# glowbs_4.net
KiCad netlist of a schematic drawn in EAGLE
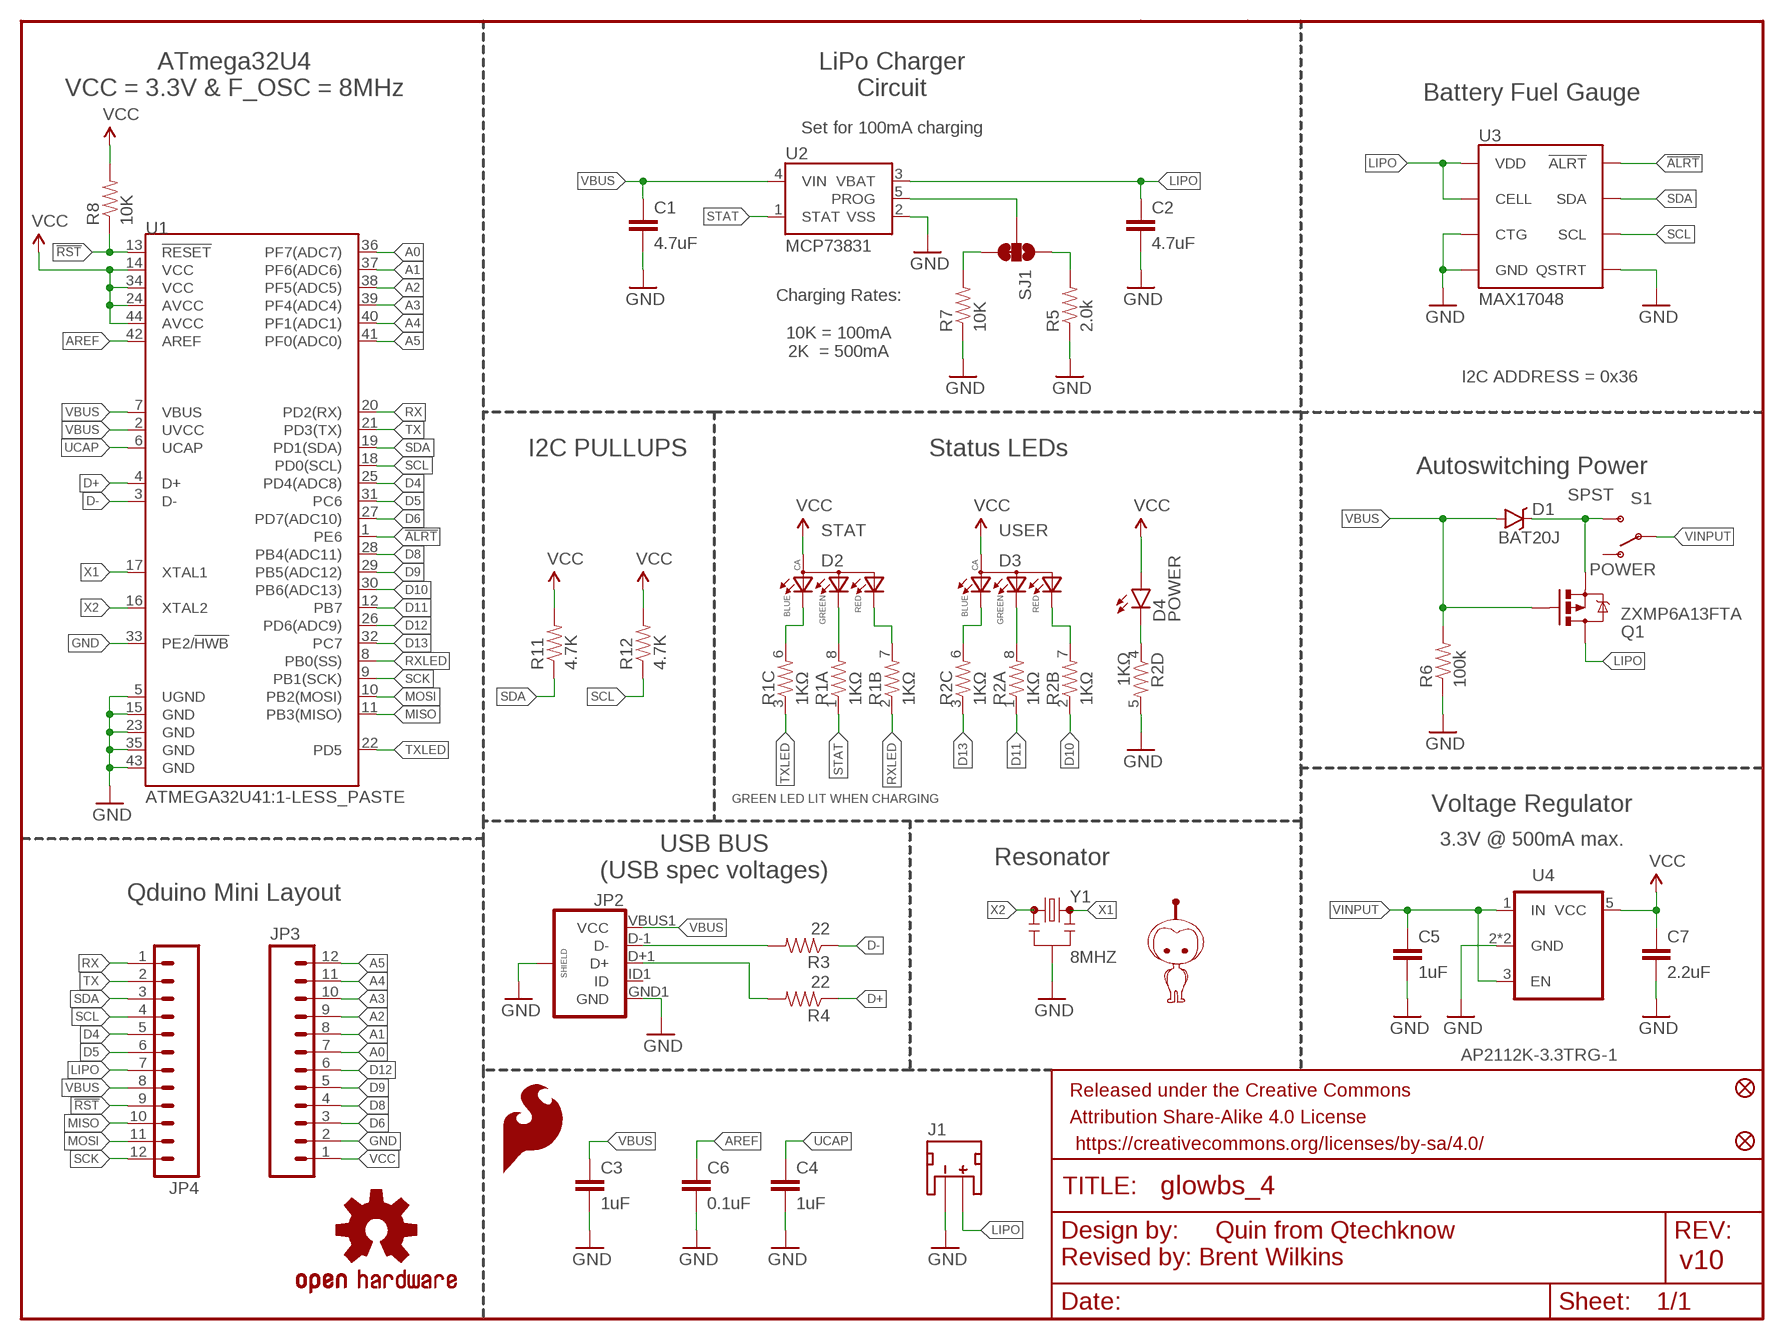
[diagram p0: schematic, sheet 1]

(export (version "E")
  (design (tool "Eeschema 10.0.6"))
  (components
    (comp (ref "C1")
      (value "4.7uF")
      (footprint "eagle-import:0603-CAP")
      (libsource (lib "eagle-import") (part "CAP0603-CAP"))
    )
    (comp (ref "C2")
      (value "4.7uF")
      (footprint "eagle-import:0603-CAP")
      (libsource (lib "eagle-import") (part "CAP0603-CAP"))
    )
    (comp (ref "C3")
      (value "1uF")
      (footprint "eagle-import:0603-CAP")
      (libsource (lib "eagle-import") (part "CAP0603-CAP"))
    )
    (comp (ref "C4")
      (value "1uF")
      (footprint "eagle-import:0603-CAP")
      (libsource (lib "eagle-import") (part "CAP0603-CAP"))
    )
    (comp (ref "C5")
      (value "1uF")
      (footprint "eagle-import:0603-CAP")
      (libsource (lib "eagle-import") (part "CAP0603-CAP"))
    )
    (comp (ref "C6")
      (value "0.1uF")
      (footprint "eagle-import:0603-CAP")
      (libsource (lib "eagle-import") (part "0.1UF-25V(+80/-20%)(0603)"))
    )
    (comp (ref "C7")
      (value "2.2uF")
      (footprint "eagle-import:0603-CAP")
      (libsource (lib "eagle-import") (part "2.2UF-10V-20%(0603)"))
    )
    (comp (ref "D1")
      (value "BAT20J")
      (footprint "eagle-import:SOD-323")
      (libsource (lib "eagle-import") (part "DIODE-SCHOTTKY-BAT20J"))
    )
    (comp (ref "D2")
      (value "0.13_RGB_LEDPLCC")
      (footprint "eagle-import:P-LCC-4-3")
      (fields (field (name "PROD_ID") "DIO-12986"))
      (libsource (lib "eagle-import") (part "0.13_RGB_LEDPLCC"))
    )
    (comp (ref "D3")
      (value "0.13_RGB_LEDPLCC")
      (footprint "eagle-import:P-LCC-4-3")
      (libsource (lib "eagle-import") (part "0.13_RGB_LEDPLCC"))
    )
    (comp (ref "D4")
      (value "POWER")
      (footprint "eagle-import:LED-0603")
      (fields (field (name "PROD_ID") "DIO-00821"))
      (libsource (lib "eagle-import") (part "LED-GREEN0603"))
    )
    (comp (ref "FID1")
      (value "FIDUCIALUFIDUCIAL")
      (footprint "eagle-import:MICRO-FIDUCIAL")
      (libsource (lib "eagle-import") (part "FIDUCIALUFIDUCIAL"))
    )
    (comp (ref "FID2")
      (value "FIDUCIALUFIDUCIAL")
      (footprint "eagle-import:MICRO-FIDUCIAL")
      (libsource (lib "eagle-import") (part "FIDUCIALUFIDUCIAL"))
    )
    (comp (ref "FRAME2")
      (value "FRAME-LETTER")
      (footprint "eagle-import:CREATIVE_COMMONS")
      (fields (field (name "DESIGNER") "NAME"))
      (libsource (lib "eagle-import") (part "FRAME-LETTER"))
    )
    (comp (ref "J1")
      (value "LiPo")
      (footprint "eagle-import:JST-2-SMD")
      (libsource (lib "eagle-import") (part "JST_2MM_MALE"))
    )
    (comp (ref "JP2")
      (value "USB_MICROB_PLUGCONN-11752")
      (footprint "eagle-import:USB-B-MICRO-SMD_V03")
      (libsource (lib "eagle-import") (part "USB_MICROB_PLUGCONN-11752"))
    )
    (comp (ref "JP3")
      (value "M12PTH")
      (footprint "eagle-import:1X12")
      (libsource (lib "eagle-import") (part "M12PTH"))
    )
    (comp (ref "JP4")
      (value "M12PTH")
      (footprint "eagle-import:1X12")
      (libsource (lib "eagle-import") (part "M12PTH"))
    )
    (comp (ref "LOGO1")
      (value "OSHW-LOGOS")
      (footprint "eagle-import:OSHW-LOGO-S")
      (libsource (lib "eagle-import") (part "OSHW-LOGOS"))
    )
    (comp (ref "LOGO2")
      (value "SFE_LOGO_FLAME.1_INCH")
      (footprint "eagle-import:SFE_LOGO_FLAME_.1")
      (libsource (lib "eagle-import") (part "SFE_LOGO_FLAME.1_INCH"))
    )
    (comp (ref "Q1")
      (value "ZXMP6A13FTA")
      (footprint "eagle-import:SOT23-3")
      (libsource (lib "eagle-import") (part "MOSFET-PCHANNEL"))
    )
    (comp (ref "R1")
      (value "1KΩ")
      (footprint "eagle-import:0603-ARV")
      (fields (field (name "PROD_ID") "RES-12985"))
      (libsource (lib "eagle-import") (part "RESISTOR-ARRAY0603-ARV"))
    )
    (comp (ref "R2")
      (value "1KΩ")
      (footprint "eagle-import:0603-ARV")
      (fields (field (name "PROD_ID") "RES-12985"))
      (libsource (lib "eagle-import") (part "RESISTOR-ARRAY0603-ARV"))
    )
    (comp (ref "R3")
      (value "22")
      (footprint "eagle-import:0603-RES")
      (libsource (lib "eagle-import") (part "RESISTOR0603"))
    )
    (comp (ref "R4")
      (value "22")
      (footprint "eagle-import:0603-RES")
      (libsource (lib "eagle-import") (part "RESISTOR0603"))
    )
    (comp (ref "R5")
      (value "2.0k")
      (footprint "eagle-import:0603-RES")
      (libsource (lib "eagle-import") (part "2.0KOHM1/10W5%(0603)"))
    )
    (comp (ref "R6")
      (value "100k")
      (footprint "eagle-import:0603-RES")
      (libsource (lib "eagle-import") (part "100KOHM-1/10W-1%(0603)"))
    )
    (comp (ref "R7")
      (value "10K")
      (footprint "eagle-import:0603-RES")
      (libsource (lib "eagle-import") (part "10KOHM-1/10W-1%(0603)0603"))
    )
    (comp (ref "R8")
      (value "10K")
      (footprint "eagle-import:0603-RES")
      (libsource (lib "eagle-import") (part "10KOHM-1/10W-1%(0603)0603"))
    )
    (comp (ref "R11")
      (value "4.7K")
      (footprint "eagle-import:0603-RES")
      (libsource (lib "eagle-import") (part "RESISTOR0603-RES"))
    )
    (comp (ref "R12")
      (value "4.7K")
      (footprint "eagle-import:0603-RES")
      (libsource (lib "eagle-import") (part "RESISTOR0603-RES"))
    )
    (comp (ref "S1")
      (value "POWER")
      (footprint "eagle-import:SWITCH-SPST-SMD-A")
      (libsource (lib "eagle-import") (part "SWITCH-SPDT-SMD-A"))
    )
    (comp (ref "SJ1")
      (value "JUMPER-PAD-3-2OF3_NC_BY_TRACE_SMALL")
      (footprint "eagle-import:PAD-JUMPER-3-2OF3_NC_BY_TRACE_YES_SILK_FULL_BOX")
      (libsource (lib "eagle-import") (part "JUMPER-PAD-3-2OF3_NC_BY_TRACE_SMALL"))
    )
    (comp (ref "U1")
      (value "ATMEGA32U41:1-LESS_PASTE")
      (footprint "eagle-import:QFN-44-NOPAD_1_1-LESS_PASTE")
      (libsource (lib "eagle-import") (part "ATMEGA32U41{colon}1-LESS_PASTE"))
    )
    (comp (ref "U2")
      (value "MCP73831")
      (footprint "eagle-import:SOT23-5")
      (libsource (lib "eagle-import") (part "MCP73831"))
    )
    (comp (ref "U3")
      (value "MAX17048")
      (footprint "eagle-import:DFN-8")
      (libsource (lib "eagle-import") (part "MAX17048DFN8"))
    )
    (comp (ref "U4")
      (value "AP2112K-3.3TRG-1")
      (footprint "eagle-import:SOT23-5")
      (libsource (lib "eagle-import") (part "LDO-TPS78233"))
    )
    (comp (ref "U5")
      (value "MIGHTYQ-L-SILK")
      (footprint "eagle-import:LOGO-LARGE-SILK")
      (libsource (lib "eagle-import") (part "MIGHTYQ-L-SILK"))
    )
    (comp (ref "Y1")
      (value "8MHZ")
      (footprint "eagle-import:RESONATOR-SMD")
      (libsource (lib "eagle-import") (part "RESONATOR8MHZ"))
    )
  )
  (nets
    (net (code "1") (name "/~{ALRT}") (class "Default")
      (node (ref "U1") (pin "1") (pinfunction "PE6_1") (pintype "bidirectional"))
      (node (ref "U3") (pin "P$5") (pinfunction "~{ALRT}_P$5") (pintype "bidirectional"))
    )
    (net (code "2") (name "/~{RST}") (class "Default")
      (node (ref "JP4") (pin "9") (pinfunction "9_9") (pintype "passive"))
      (node (ref "R8") (pin "1") (pinfunction "1_1") (pintype "passive"))
      (node (ref "U1") (pin "13") (pinfunction "~{RESET}_13") (pintype "bidirectional"))
    )
    (net (code "3") (name "A0") (class "Default")
      (node (ref "JP3") (pin "7") (pinfunction "7_7") (pintype "passive"))
      (node (ref "U1") (pin "36") (pinfunction "PF7(ADC7)_36") (pintype "bidirectional"))
    )
    (net (code "4") (name "A1") (class "Default")
      (node (ref "JP3") (pin "8") (pinfunction "8_8") (pintype "passive"))
      (node (ref "U1") (pin "37") (pinfunction "PF6(ADC6)_37") (pintype "bidirectional"))
    )
    (net (code "5") (name "A2") (class "Default")
      (node (ref "JP3") (pin "9") (pinfunction "9_9") (pintype "passive"))
      (node (ref "U1") (pin "38") (pinfunction "PF5(ADC5)_38") (pintype "bidirectional"))
    )
    (net (code "6") (name "A3") (class "Default")
      (node (ref "JP3") (pin "10") (pinfunction "10_10") (pintype "passive"))
      (node (ref "U1") (pin "39") (pinfunction "PF4(ADC4)_39") (pintype "bidirectional"))
    )
    (net (code "7") (name "A4") (class "Default")
      (node (ref "JP3") (pin "11") (pinfunction "11_11") (pintype "passive"))
      (node (ref "U1") (pin "40") (pinfunction "PF1(ADC1)_40") (pintype "bidirectional"))
    )
    (net (code "8") (name "A5") (class "Default")
      (node (ref "JP3") (pin "12") (pinfunction "12_12") (pintype "passive"))
      (node (ref "U1") (pin "41") (pinfunction "PF0(ADC0)_41") (pintype "bidirectional"))
    )
    (net (code "9") (name "AREF") (class "Default")
      (node (ref "C6") (pin "1") (pinfunction "1_1") (pintype "passive"))
      (node (ref "U1") (pin "42") (pinfunction "AREF_42") (pintype "bidirectional"))
    )
    (net (code "10") (name "D+") (class "Default")
      (node (ref "R4") (pin "1") (pinfunction "1_1") (pintype "passive"))
      (node (ref "U1") (pin "4") (pinfunction "D+_4") (pintype "bidirectional"))
    )
    (net (code "11") (name "D-") (class "Default")
      (node (ref "R3") (pin "1") (pinfunction "1_1") (pintype "passive"))
      (node (ref "U1") (pin "3") (pinfunction "D-_3") (pintype "bidirectional"))
    )
    (net (code "12") (name "D4") (class "Default")
      (node (ref "JP4") (pin "5") (pinfunction "5_5") (pintype "passive"))
      (node (ref "U1") (pin "25") (pinfunction "PD4(ADC8)_25") (pintype "bidirectional"))
    )
    (net (code "13") (name "D5") (class "Default")
      (node (ref "JP4") (pin "6") (pinfunction "6_6") (pintype "passive"))
      (node (ref "U1") (pin "31") (pinfunction "PC6_31") (pintype "bidirectional"))
    )
    (net (code "14") (name "D6") (class "Default")
      (node (ref "JP3") (pin "3") (pinfunction "3_3") (pintype "passive"))
      (node (ref "U1") (pin "27") (pinfunction "PD7(ADC10)_27") (pintype "bidirectional"))
    )
    (net (code "15") (name "D8") (class "Default")
      (node (ref "JP3") (pin "4") (pinfunction "4_4") (pintype "passive"))
      (node (ref "U1") (pin "28") (pinfunction "PB4(ADC11)_28") (pintype "bidirectional"))
    )
    (net (code "16") (name "D9") (class "Default")
      (node (ref "JP3") (pin "5") (pinfunction "5_5") (pintype "passive"))
      (node (ref "U1") (pin "29") (pinfunction "PB5(ADC12)_29") (pintype "bidirectional"))
    )
    (net (code "17") (name "D10") (class "Default")
      (node (ref "R2") (pin "2") (pinfunction "1_2") (pintype "passive"))
      (node (ref "U1") (pin "30") (pinfunction "PB6(ADC13)_30") (pintype "bidirectional"))
    )
    (net (code "18") (name "D11") (class "Default")
      (node (ref "R2") (pin "1") (pinfunction "1_1") (pintype "passive"))
      (node (ref "U1") (pin "12") (pinfunction "PB7_12") (pintype "bidirectional"))
    )
    (net (code "19") (name "D12") (class "Default")
      (node (ref "JP3") (pin "6") (pinfunction "6_6") (pintype "passive"))
      (node (ref "U1") (pin "26") (pinfunction "PD6(ADC9)_26") (pintype "bidirectional"))
    )
    (net (code "20") (name "D13") (class "Default")
      (node (ref "R2") (pin "3") (pinfunction "1_3") (pintype "passive"))
      (node (ref "U1") (pin "32") (pinfunction "PC7_32") (pintype "bidirectional"))
    )
    (net (code "21") (name "GND") (class "Default")
      (node (ref "C1") (pin "2") (pinfunction "2_2") (pintype "passive"))
      (node (ref "C2") (pin "2") (pinfunction "2_2") (pintype "passive"))
      (node (ref "C3") (pin "2") (pinfunction "2_2") (pintype "passive"))
      (node (ref "C4") (pin "2") (pinfunction "2_2") (pintype "passive"))
      (node (ref "C5") (pin "2") (pinfunction "2_2") (pintype "passive"))
      (node (ref "C6") (pin "2") (pinfunction "2_2") (pintype "passive"))
      (node (ref "C7") (pin "2") (pinfunction "2_2") (pintype "passive"))
      (node (ref "J1") (pin "1") (pinfunction "-_1") (pintype "bidirectional"))
      (node (ref "JP2") (pin "GND1") (pinfunction "GND_GND1") (pintype "bidirectional"))
      (node (ref "JP2") (pin "SHIELD1") (pinfunction "SHIELD_SHIELD1") (pintype "bidirectional"))
      (node (ref "JP2") (pin "SHIELD2") (pinfunction "SHIELD_SHIELD2") (pintype "bidirectional"))
      (node (ref "JP2") (pin "SHIELD3") (pinfunction "SHIELD_SHIELD3") (pintype "bidirectional"))
      (node (ref "JP3") (pin "2") (pinfunction "2_2") (pintype "passive"))
      (node (ref "R2") (pin "5") (pinfunction "2_5") (pintype "passive"))
      (node (ref "R5") (pin "1") (pinfunction "1_1") (pintype "passive"))
      (node (ref "R6") (pin "1") (pinfunction "1_1") (pintype "passive"))
      (node (ref "R7") (pin "1") (pinfunction "1_1") (pintype "passive"))
      (node (ref "U1") (pin "15") (pinfunction "GND_15") (pintype "bidirectional"))
      (node (ref "U1") (pin "23") (pinfunction "GND_23") (pintype "bidirectional"))
      (node (ref "U1") (pin "33") (pinfunction "PE2/~{HWB}_33") (pintype "bidirectional"))
      (node (ref "U1") (pin "35") (pinfunction "GND_35") (pintype "bidirectional"))
      (node (ref "U1") (pin "43") (pinfunction "GND_43") (pintype "bidirectional"))
      (node (ref "U1") (pin "5") (pinfunction "UGND_5") (pintype "bidirectional"))
      (node (ref "U2") (pin "2") (pinfunction "VSS_2") (pintype "power_in"))
      (node (ref "U3") (pin "P$1") (pinfunction "CTG_P$1") (pintype "input"))
      (node (ref "U3") (pin "P$4") (pinfunction "GND_P$4") (pintype "bidirectional"))
      (node (ref "U3") (pin "P$6") (pinfunction "QSTRT_P$6") (pintype "bidirectional"))
      (node (ref "U3") (pin "P$9") (pinfunction "GND_P$9") (pintype "bidirectional"))
      (node (ref "U4") (pin "2") (pinfunction "GND_2") (pintype "input"))
      (node (ref "U4") (pin "4") (pinfunction "GND_4") (pintype "input"))
      (node (ref "Y1") (pin "2") (pinfunction "2_2") (pintype "passive"))
    )
    (net (code "22") (name "LIPO") (class "Default")
      (node (ref "C2") (pin "1") (pinfunction "1_1") (pintype "passive"))
      (node (ref "J1") (pin "2") (pinfunction "+_2") (pintype "bidirectional"))
      (node (ref "JP4") (pin "7") (pinfunction "7_7") (pintype "passive"))
      (node (ref "Q1") (pin "3") (pinfunction "D_3") (pintype "passive"))
      (node (ref "U2") (pin "3") (pinfunction "VBAT_3") (pintype "power_in"))
      (node (ref "U3") (pin "P$2") (pinfunction "CELL_P$2") (pintype "input"))
      (node (ref "U3") (pin "P$3") (pinfunction "VDD_P$3") (pintype "bidirectional"))
    )
    (net (code "23") (name "MISO") (class "Default")
      (node (ref "JP4") (pin "10") (pinfunction "10_10") (pintype "passive"))
      (node (ref "U1") (pin "11") (pinfunction "PB3(MISO)_11") (pintype "bidirectional"))
    )
    (net (code "24") (name "MOSI") (class "Default")
      (node (ref "JP4") (pin "11") (pinfunction "11_11") (pintype "passive"))
      (node (ref "U1") (pin "10") (pinfunction "PB2(MOSI)_10") (pintype "bidirectional"))
    )
    (net (code "25") (name "Net-(D2-BLUE)") (class "Default")
      (node (ref "D2") (pin "3") (pinfunction "BLUE_3") (pintype "passive"))
      (node (ref "R1") (pin "6") (pinfunction "2_6") (pintype "passive"))
    )
    (net (code "26") (name "Net-(D2-GREEN)") (class "Default")
      (node (ref "D2") (pin "2") (pinfunction "GREEN_2") (pintype "passive"))
      (node (ref "R1") (pin "8") (pinfunction "2_8") (pintype "passive"))
    )
    (net (code "27") (name "Net-(D2-RED)") (class "Default")
      (node (ref "D2") (pin "1") (pinfunction "RED_1") (pintype "passive"))
      (node (ref "R1") (pin "7") (pinfunction "2_7") (pintype "passive"))
    )
    (net (code "28") (name "Net-(D3-BLUE)") (class "Default")
      (node (ref "D3") (pin "3") (pinfunction "BLUE_3") (pintype "passive"))
      (node (ref "R2") (pin "6") (pinfunction "2_6") (pintype "passive"))
    )
    (net (code "29") (name "Net-(D3-GREEN)") (class "Default")
      (node (ref "D3") (pin "2") (pinfunction "GREEN_2") (pintype "passive"))
      (node (ref "R2") (pin "8") (pinfunction "2_8") (pintype "passive"))
    )
    (net (code "30") (name "Net-(D3-RED)") (class "Default")
      (node (ref "D3") (pin "1") (pinfunction "RED_1") (pintype "passive"))
      (node (ref "R2") (pin "7") (pinfunction "2_7") (pintype "passive"))
    )
    (net (code "31") (name "Net-(JP2-D+)") (class "Default")
      (node (ref "JP2") (pin "D+1") (pinfunction "D+_D+1") (pintype "bidirectional"))
      (node (ref "R4") (pin "2") (pinfunction "2_2") (pintype "passive"))
    )
    (net (code "32") (name "Net-(JP2-D-)") (class "Default")
      (node (ref "JP2") (pin "D-1") (pinfunction "D-_D-1") (pintype "bidirectional"))
      (node (ref "R3") (pin "2") (pinfunction "2_2") (pintype "passive"))
    )
    (net (code "33") (name "Net-(Q1-S)") (class "Default")
      (node (ref "D1") (pin "C") (pinfunction "C_C") (pintype "passive"))
      (node (ref "Q1") (pin "2") (pinfunction "S_2") (pintype "passive"))
      (node (ref "S1") (pin "3") (pinfunction "S_3") (pintype "passive"))
    )
    (net (code "34") (name "Net-(R2D-1)") (class "Default")
      (node (ref "D4") (pin "C") (pinfunction "C_C") (pintype "passive"))
      (node (ref "R2") (pin "4") (pinfunction "1_4") (pintype "passive"))
    )
    (net (code "35") (name "Net-(R5-Pad2)") (class "Default")
      (node (ref "R5") (pin "2") (pinfunction "2_2") (pintype "passive"))
      (node (ref "SJ1") (pin "1") (pinfunction "1_1") (pintype "passive"))
    )
    (net (code "36") (name "Net-(R7-Pad2)") (class "Default")
      (node (ref "R7") (pin "2") (pinfunction "2_2") (pintype "passive"))
      (node (ref "SJ1") (pin "3") (pinfunction "3_3") (pintype "passive"))
    )
    (net (code "37") (name "Net-(U2-PROG)") (class "Default")
      (node (ref "SJ1") (pin "2") (pinfunction "2_2") (pintype "passive"))
      (node (ref "U2") (pin "5") (pinfunction "PROG_5") (pintype "input"))
    )
    (net (code "38") (name "RX") (class "Default")
      (node (ref "JP4") (pin "1") (pinfunction "1_1") (pintype "passive"))
      (node (ref "U1") (pin "20") (pinfunction "PD2(RX)_20") (pintype "bidirectional"))
    )
    (net (code "39") (name "RXLED") (class "Default")
      (node (ref "R1") (pin "2") (pinfunction "1_2") (pintype "passive"))
      (node (ref "U1") (pin "8") (pinfunction "PB0(SS)_8") (pintype "bidirectional"))
    )
    (net (code "40") (name "SCK") (class "Default")
      (node (ref "JP4") (pin "12") (pinfunction "12_12") (pintype "passive"))
      (node (ref "U1") (pin "9") (pinfunction "PB1(SCK)_9") (pintype "bidirectional"))
    )
    (net (code "41") (name "SCL") (class "Default")
      (node (ref "JP4") (pin "4") (pinfunction "4_4") (pintype "passive"))
      (node (ref "R12") (pin "1") (pinfunction "1_1") (pintype "passive"))
      (node (ref "U1") (pin "18") (pinfunction "PD0(SCL)_18") (pintype "bidirectional"))
      (node (ref "U3") (pin "P$7") (pinfunction "SCL_P$7") (pintype "output"))
    )
    (net (code "42") (name "SDA") (class "Default")
      (node (ref "JP4") (pin "3") (pinfunction "3_3") (pintype "passive"))
      (node (ref "R11") (pin "1") (pinfunction "1_1") (pintype "passive"))
      (node (ref "U1") (pin "19") (pinfunction "PD1(SDA)_19") (pintype "bidirectional"))
      (node (ref "U3") (pin "P$8") (pinfunction "SDA_P$8") (pintype "input"))
    )
    (net (code "43") (name "STAT") (class "Default")
      (node (ref "R1") (pin "1") (pinfunction "1_1") (pintype "passive"))
      (node (ref "U2") (pin "1") (pinfunction "STAT_1") (pintype "output"))
    )
    (net (code "44") (name "TX") (class "Default")
      (node (ref "JP4") (pin "2") (pinfunction "2_2") (pintype "passive"))
      (node (ref "U1") (pin "21") (pinfunction "PD3(TX)_21") (pintype "bidirectional"))
    )
    (net (code "45") (name "TXLED") (class "Default")
      (node (ref "R1") (pin "3") (pinfunction "1_3") (pintype "passive"))
      (node (ref "U1") (pin "22") (pinfunction "PD5_22") (pintype "bidirectional"))
    )
    (net (code "46") (name "UCAP") (class "Default")
      (node (ref "C4") (pin "1") (pinfunction "1_1") (pintype "passive"))
      (node (ref "U1") (pin "6") (pinfunction "UCAP_6") (pintype "bidirectional"))
    )
    (net (code "47") (name "VBUS") (class "Default")
      (node (ref "C1") (pin "1") (pinfunction "1_1") (pintype "passive"))
      (node (ref "C3") (pin "1") (pinfunction "1_1") (pintype "passive"))
      (node (ref "D1") (pin "A") (pinfunction "A_A") (pintype "passive"))
      (node (ref "JP2") (pin "VBUS1") (pinfunction "VCC_VBUS1") (pintype "bidirectional"))
      (node (ref "JP4") (pin "8") (pinfunction "8_8") (pintype "passive"))
      (node (ref "Q1") (pin "1") (pinfunction "G_1") (pintype "passive"))
      (node (ref "R6") (pin "2") (pinfunction "2_2") (pintype "passive"))
      (node (ref "U1") (pin "2") (pinfunction "UVCC_2") (pintype "bidirectional"))
      (node (ref "U1") (pin "7") (pinfunction "VBUS_7") (pintype "bidirectional"))
      (node (ref "U2") (pin "4") (pinfunction "VIN_4") (pintype "power_in"))
    )
    (net (code "48") (name "VCC") (class "Default")
      (node (ref "C7") (pin "1") (pinfunction "1_1") (pintype "passive"))
      (node (ref "D2") (pin "4") (pinfunction "ANODE_4") (pintype "passive"))
      (node (ref "D3") (pin "4") (pinfunction "ANODE_4") (pintype "passive"))
      (node (ref "D4") (pin "A") (pinfunction "A_A") (pintype "passive"))
      (node (ref "JP3") (pin "1") (pinfunction "1_1") (pintype "passive"))
      (node (ref "R11") (pin "2") (pinfunction "2_2") (pintype "passive"))
      (node (ref "R12") (pin "2") (pinfunction "2_2") (pintype "passive"))
      (node (ref "R8") (pin "2") (pinfunction "2_2") (pintype "passive"))
      (node (ref "U1") (pin "14") (pinfunction "VCC_14") (pintype "bidirectional"))
      (node (ref "U1") (pin "24") (pinfunction "AVCC_24") (pintype "bidirectional"))
      (node (ref "U1") (pin "34") (pinfunction "VCC_34") (pintype "bidirectional"))
      (node (ref "U1") (pin "44") (pinfunction "AVCC_44") (pintype "bidirectional"))
      (node (ref "U4") (pin "5") (pinfunction "VCC_5") (pintype "power_in"))
    )
    (net (code "49") (name "VINPUT") (class "Default")
      (node (ref "C5") (pin "1") (pinfunction "1_1") (pintype "passive"))
      (node (ref "S1") (pin "2") (pinfunction "P_2") (pintype "passive"))
      (node (ref "U4") (pin "1") (pinfunction "IN_1") (pintype "input"))
      (node (ref "U4") (pin "3") (pinfunction "EN_3") (pintype "input"))
    )
    (net (code "50") (name "X1") (class "Default")
      (node (ref "U1") (pin "17") (pinfunction "XTAL1_17") (pintype "bidirectional"))
      (node (ref "Y1") (pin "3") (pinfunction "3_3") (pintype "passive"))
    )
    (net (code "51") (name "X2") (class "Default")
      (node (ref "U1") (pin "16") (pinfunction "XTAL2_16") (pintype "bidirectional"))
      (node (ref "Y1") (pin "1") (pinfunction "1_1") (pintype "passive"))
    )
    (net (code "52") (name "unconnected-(J1-PAD1-PadNC1)") (class "Default")
      (node (ref "J1") (pin "NC1") (pinfunction "PAD1_NC1") (pintype "bidirectional"))
    )
    (net (code "53") (name "unconnected-(J1-PAD2-PadNC2)") (class "Default")
      (node (ref "J1") (pin "NC2") (pinfunction "PAD2_NC2") (pintype "bidirectional"))
    )
    (net (code "54") (name "unconnected-(JP2-ID-PadID1)") (class "Default")
      (node (ref "JP2") (pin "ID1") (pinfunction "ID_ID1") (pintype "bidirectional"))
    )
    (net (code "55") (name "unconnected-(S1-O-Pad1)") (class "Default")
      (node (ref "S1") (pin "1") (pinfunction "O_1") (pintype "passive"))
    )
  )
)
